# AFE4900.net
KiCad netlist of a schematic drawn in Altium Designer
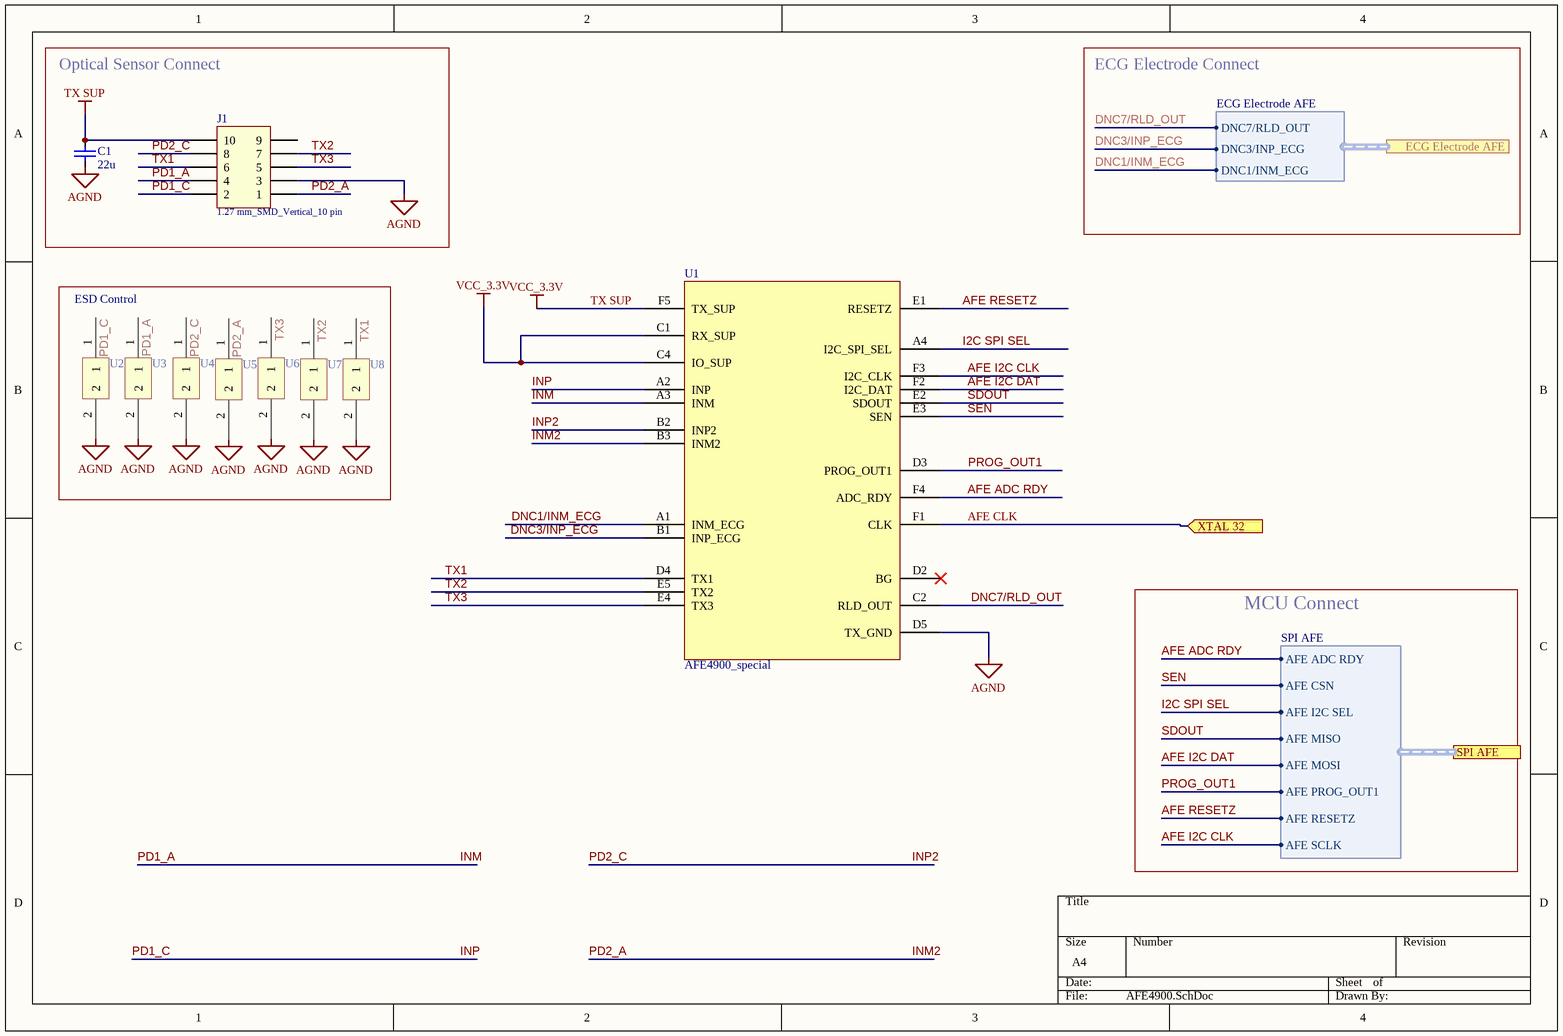
[diagram p0: AFE4900.SchDoc]

(export (version "E")
  (design (tool "Eeschema 10.0.6"))
  (components
    (comp (ref "C1")
      (value "22u")
      (footprint "Lib_C:CAPC1608X05N")
      (description "Kondensator 22u 0603")
      (libsource (lib "Lib_C") (part "C_22u_0603"))
    )
    (comp (ref "J1")
      (value "1.27 mm_SMD_Vertical_10 pin")
      (footprint "62131021021")
      (description "Pin Header WR-PHD, pitch 1.27 mm, SMD, Vertical, dual row, 10 pin")
      (fields (field (name "PART NUMBER") "62131021021") (field (name "PUBLISHER") "Wurth Elektronik"))
      (libsource (lib "Pin Header WR-PHD_1.27mm") (part "62131021021"))
    )
    (comp (ref "U1")
      (value "AFE4900_special")
      (footprint "AFE4900_Breakout")
      (description "Synchronized_ECG_and_PPG_AFE")
      (libsource (lib "Lib_IC") (part "AFE4900_special"))
    )
    (comp (ref "U2")
      (value "TPD1E10B06DPYR")
      (footprint "TPD1E10B06DPYR_0402")
      (description "TPD1E10B06DPYR 0402")
      (libsource (lib "Lib_D") (part "TPD1E10B06DPYR"))
    )
    (comp (ref "U3")
      (value "TPD1E10B06DPYR")
      (footprint "TPD1E10B06DPYR_0402")
      (description "TPD1E10B06DPYR 0402")
      (libsource (lib "Lib_D") (part "TPD1E10B06DPYR"))
    )
    (comp (ref "U4")
      (value "TPD1E10B06DPYR")
      (footprint "TPD1E10B06DPYR_0402")
      (description "TPD1E10B06DPYR 0402")
      (libsource (lib "Lib_D") (part "TPD1E10B06DPYR"))
    )
    (comp (ref "U5")
      (value "TPD1E10B06DPYR")
      (footprint "TPD1E10B06DPYR_0402")
      (description "TPD1E10B06DPYR 0402")
      (libsource (lib "Lib_D") (part "TPD1E10B06DPYR"))
    )
    (comp (ref "U6")
      (value "TPD1E10B06DPYR")
      (footprint "TPD1E10B06DPYR_0402")
      (description "TPD1E10B06DPYR 0402")
      (libsource (lib "Lib_D") (part "TPD1E10B06DPYR"))
    )
    (comp (ref "U7")
      (value "TPD1E10B06DPYR")
      (footprint "TPD1E10B06DPYR_0402")
      (description "TPD1E10B06DPYR 0402")
      (libsource (lib "Lib_D") (part "TPD1E10B06DPYR"))
    )
    (comp (ref "U8")
      (value "TPD1E10B06DPYR")
      (footprint "TPD1E10B06DPYR_0402")
      (description "TPD1E10B06DPYR 0402")
      (libsource (lib "Lib_D") (part "TPD1E10B06DPYR"))
    )
  )
  (nets
    (net (code "5") (name "/AFE ADC RDY") (class "Default")
      (node (ref "U1") (pin "F4") (pinfunction "ADC_RDY_F4") (pintype "passive"))
    )
    (net (code "6") (name "/AFE CLK") (class "Default")
      (node (ref "U1") (pin "F1") (pinfunction "CLK_F1") (pintype "passive"))
    )
    (net (code "7") (name "/AFE I2C CLK") (class "Default")
      (node (ref "U1") (pin "F3") (pinfunction "I2C_CLK_F3") (pintype "passive"))
    )
    (net (code "8") (name "/AFE I2C DAT") (class "Default")
      (node (ref "U1") (pin "F2") (pinfunction "I2C_DAT_F2") (pintype "passive"))
    )
    (net (code "9") (name "/AFE RESETZ") (class "Default")
      (node (ref "U1") (pin "E1") (pinfunction "RESETZ_E1") (pintype "passive"))
    )
    (net (code "10") (name "/DNC1{slash}INM_ECG") (class "Default")
      (node (ref "U1") (pin "A1") (pinfunction "INM_ECG_A1") (pintype "passive"))
    )
    (net (code "11") (name "/DNC3{slash}INP_ECG") (class "Default")
      (node (ref "U1") (pin "B1") (pinfunction "INP_ECG_B1") (pintype "passive"))
    )
    (net (code "12") (name "/DNC7{slash}RLD_OUT") (class "Default")
      (node (ref "U1") (pin "C2") (pinfunction "RLD_OUT_C2") (pintype "passive"))
    )
    (net (code "13") (name "/I2C SPI SEL") (class "Default")
      (node (ref "U1") (pin "A4") (pinfunction "I2C_SPI_SEL_A4") (pintype "passive"))
    )
    (net (code "14") (name "/INM") (class "Default")
      (node (ref "J1") (pin "4") (pinfunction "4_4") (pintype "passive"))
      (node (ref "U1") (pin "A3") (pinfunction "INM_A3") (pintype "passive"))
      (node (ref "U3") (pin "1") (pinfunction "1_1") (pintype "passive"))
    )
    (net (code "15") (name "/INM2") (class "Default")
      (node (ref "J1") (pin "1") (pinfunction "1_1") (pintype "passive"))
      (node (ref "U1") (pin "B3") (pinfunction "INM2_B3") (pintype "passive"))
      (node (ref "U5") (pin "1") (pinfunction "1_1") (pintype "passive"))
    )
    (net (code "16") (name "/INP") (class "Default")
      (node (ref "J1") (pin "2") (pinfunction "2_2") (pintype "passive"))
      (node (ref "U1") (pin "A2") (pinfunction "INP_A2") (pintype "passive"))
      (node (ref "U2") (pin "1") (pinfunction "1_1") (pintype "passive"))
    )
    (net (code "17") (name "/INP2") (class "Default")
      (node (ref "J1") (pin "8") (pinfunction "8_8") (pintype "passive"))
      (node (ref "U1") (pin "B2") (pinfunction "INP2_B2") (pintype "passive"))
      (node (ref "U4") (pin "1") (pinfunction "1_1") (pintype "passive"))
    )
    (net (code "18") (name "/PROG_OUT1") (class "Default")
      (node (ref "U1") (pin "D3") (pinfunction "PROG_OUT1_D3") (pintype "passive"))
    )
    (net (code "19") (name "/SDOUT") (class "Default")
      (node (ref "U1") (pin "E2") (pinfunction "SDOUT_E2") (pintype "passive"))
    )
    (net (code "20") (name "/SEN") (class "Default")
      (node (ref "U1") (pin "E3") (pinfunction "SEN_E3") (pintype "passive"))
    )
    (net (code "21") (name "/TX1") (class "Default")
      (node (ref "J1") (pin "6") (pinfunction "6_6") (pintype "passive"))
      (node (ref "U1") (pin "D4") (pinfunction "TX1_D4") (pintype "passive"))
      (node (ref "U8") (pin "1") (pinfunction "1_1") (pintype "passive"))
    )
    (net (code "22") (name "/TX2") (class "Default")
      (node (ref "J1") (pin "7") (pinfunction "7_7") (pintype "passive"))
      (node (ref "U1") (pin "E5") (pinfunction "TX2_E5") (pintype "passive"))
      (node (ref "U7") (pin "1") (pinfunction "1_1") (pintype "passive"))
    )
    (net (code "23") (name "/TX3") (class "Default")
      (node (ref "J1") (pin "5") (pinfunction "5_5") (pintype "passive"))
      (node (ref "U1") (pin "E4") (pinfunction "TX3_E4") (pintype "passive"))
      (node (ref "U6") (pin "1") (pinfunction "1_1") (pintype "passive"))
    )
    (net (code "26") (name "AGND") (class "Default")
      (node (ref "C1") (pin "1") (pinfunction "1_1") (pintype "passive"))
      (node (ref "J1") (pin "3") (pinfunction "3_3") (pintype "passive"))
      (node (ref "U1") (pin "D5") (pinfunction "TX_GND_D5") (pintype "passive"))
      (node (ref "U2") (pin "2") (pinfunction "2_2") (pintype "passive"))
      (node (ref "U3") (pin "2") (pinfunction "2_2") (pintype "passive"))
      (node (ref "U4") (pin "2") (pinfunction "2_2") (pintype "passive"))
      (node (ref "U5") (pin "2") (pinfunction "2_2") (pintype "passive"))
      (node (ref "U6") (pin "2") (pinfunction "2_2") (pintype "passive"))
      (node (ref "U7") (pin "2") (pinfunction "2_2") (pintype "passive"))
      (node (ref "U8") (pin "2") (pinfunction "2_2") (pintype "passive"))
    )
    (net (code "27") (name "TX SUP") (class "Default")
      (node (ref "C1") (pin "2") (pinfunction "2_2") (pintype "passive"))
      (node (ref "J1") (pin "10") (pinfunction "10_10") (pintype "passive"))
      (node (ref "U1") (pin "C1") (pinfunction "RX_SUP_C1") (pintype "passive"))
      (node (ref "U1") (pin "C4") (pinfunction "IO_SUP_C4") (pintype "passive"))
      (node (ref "U1") (pin "F5") (pinfunction "TX_SUP_F5") (pintype "passive"))
    )
    (net (code "28") (name "unconnected-(J1-Pad9)") (class "Default")
      (node (ref "J1") (pin "9") (pinfunction "9_9") (pintype "passive"))
    )
    (net (code "29") (name "unconnected-(U1-BG-PadD2)") (class "Default")
      (node (ref "U1") (pin "D2") (pinfunction "BG_D2") (pintype "passive+no_connect"))
    )
  )
)
